# buttons.net
KiCad netlist of a schematic drawn in Altium Designer
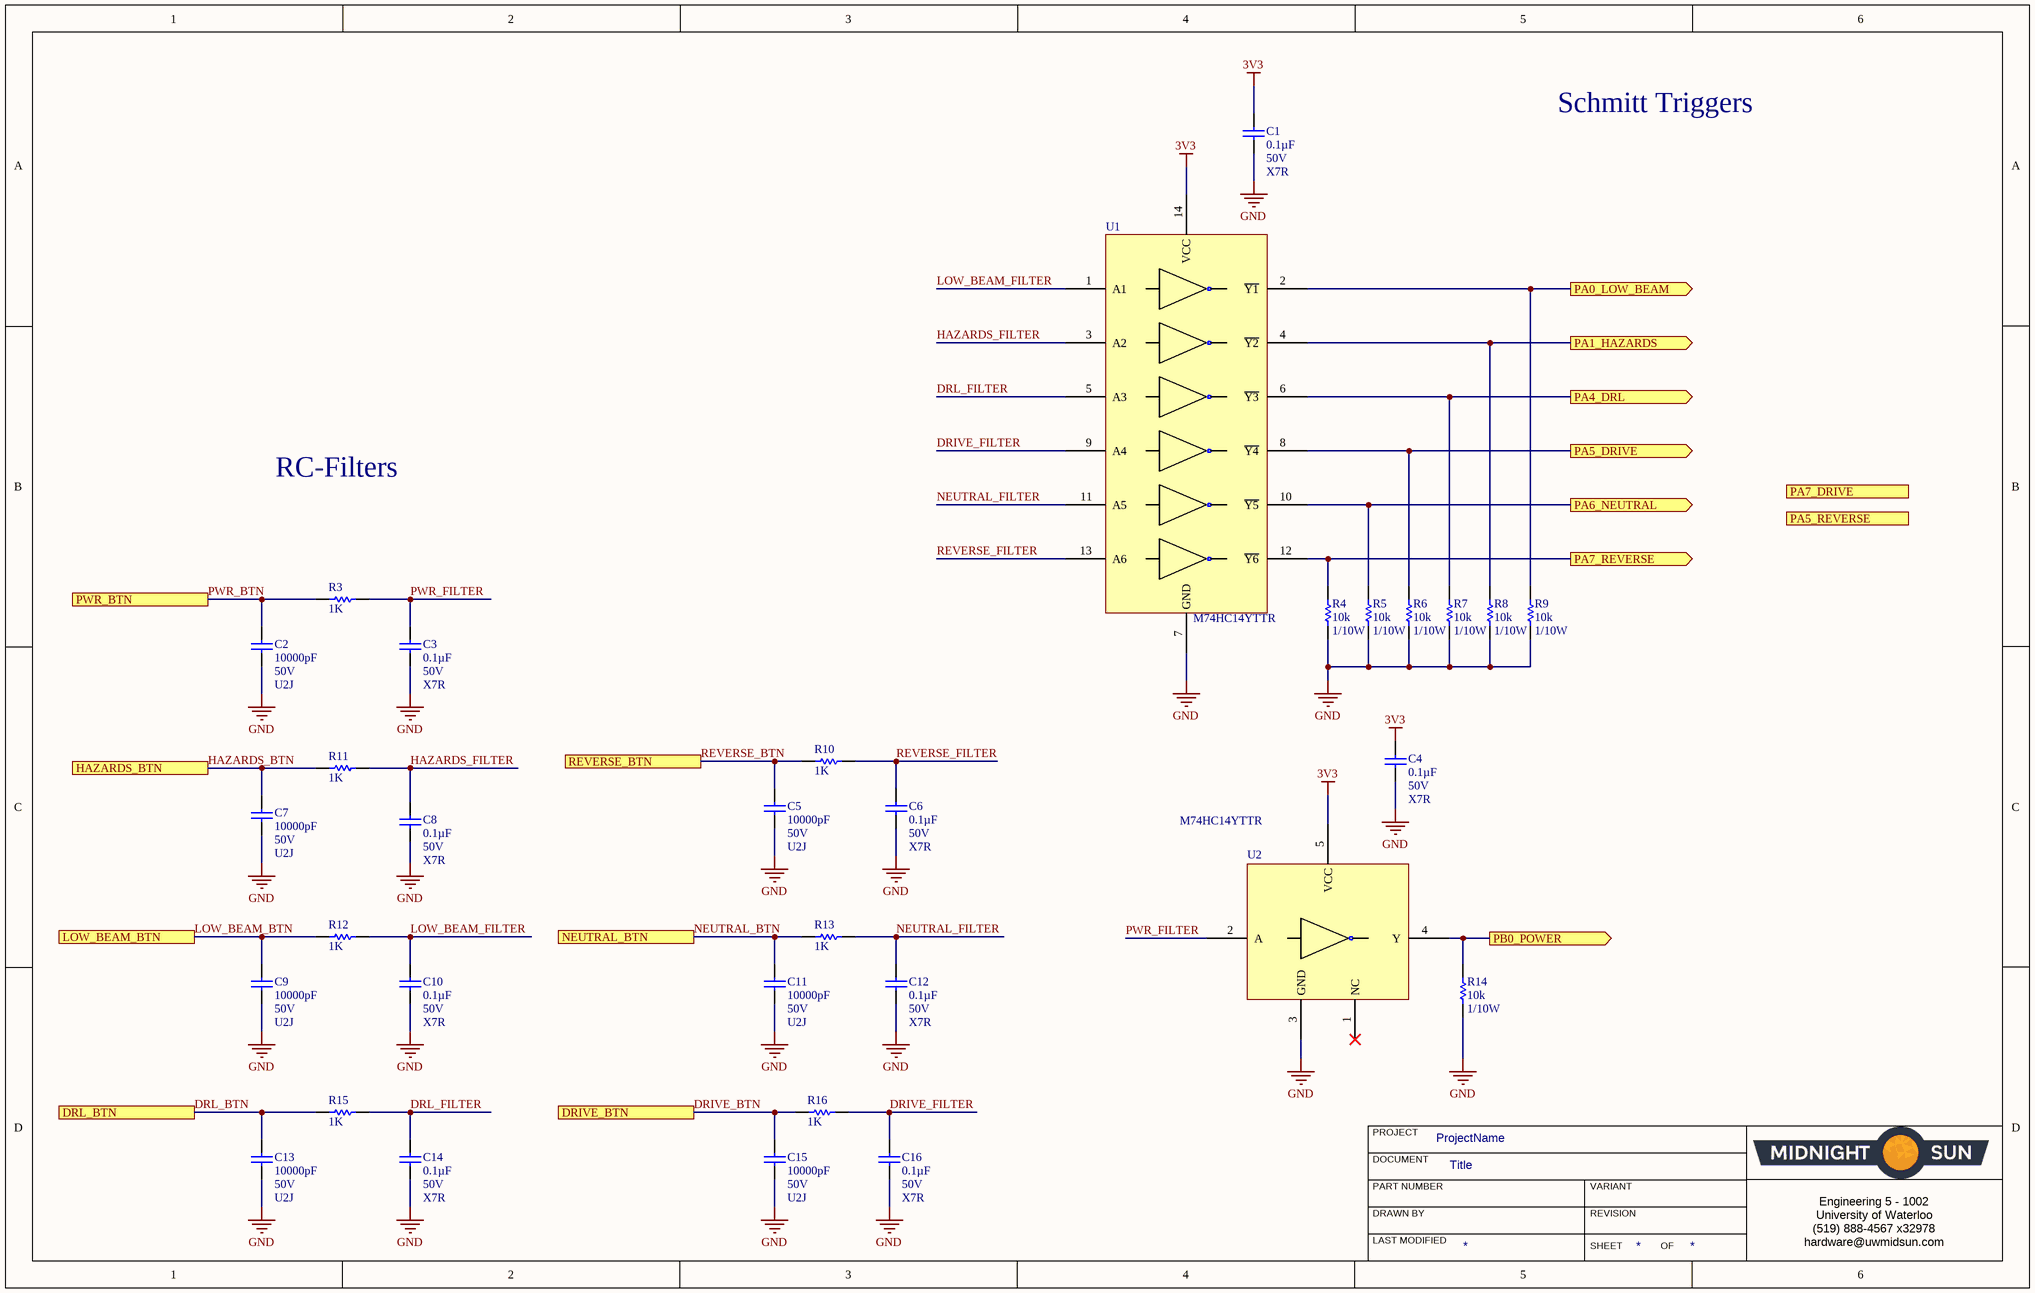
[diagram p0: buttons.SchDoc]

(export (version "E")
  (design (tool "Eeschema 10.0.6"))
  (components
    (comp (ref "C1")
      (value "CAP CER 0.1UF 50V 10% X7R 0603")
      (footprint "CAP, 0603")
      (description "0.10µF ±10% 50V Ceramic Capacitor X7R 0603 (1608 Metric)")
      (fields
        (field (name "TOLERANCE") "±10%")
        (field (name "CAPACITANCE") "0.1µF")
        (field (name "VOLTAGE") "50V")
        (field (name "TEMPERATURE COEFFICIENT") "X7R")
      )
      (libsource (lib "Schematic Diagrams") (part "CAP CER 0.1UF 50V 10% X7R 0603"))
    )
    (comp (ref "C2")
      (value "CAP CER 10nF 50V 5% X7R 0603")
      (footprint "CAP, 0603")
      (description "10000pF ±5% 50V Ceramic Capacitor U2J 0603 (1608 Metric)")
      (fields
        (field (name "TOLERANCE") "±5%")
        (field (name "CAPACITANCE") "10000pF")
        (field (name "VOLTAGE") "50V")
        (field (name "TEMPERATURE COEFFICIENT") "U2J")
      )
      (libsource (lib "altium-import") (part "root_0_CAP CER 10nF 50V 5% X7R 0603_"))
    )
    (comp (ref "C3")
      (value "CAP CER 0.1UF 50V 10% X7R 0603")
      (footprint "CAP, 0603")
      (description "0.10µF ±10% 50V Ceramic Capacitor X7R 0603 (1608 Metric)")
      (fields
        (field (name "TOLERANCE") "±10%")
        (field (name "CAPACITANCE") "0.1µF")
        (field (name "VOLTAGE") "50V")
        (field (name "TEMPERATURE COEFFICIENT") "X7R")
      )
      (libsource (lib "Schematic Diagrams") (part "CAP CER 0.1UF 50V 10% X7R 0603"))
    )
    (comp (ref "C4")
      (value "CAP CER 0.1UF 50V 10% X7R 0603")
      (footprint "CAP, 0603")
      (description "0.10µF ±10% 50V Ceramic Capacitor X7R 0603 (1608 Metric)")
      (fields
        (field (name "TOLERANCE") "±10%")
        (field (name "CAPACITANCE") "0.1µF")
        (field (name "VOLTAGE") "50V")
        (field (name "TEMPERATURE COEFFICIENT") "X7R")
      )
      (libsource (lib "Schematic Diagrams") (part "CAP CER 0.1UF 50V 10% X7R 0603"))
    )
    (comp (ref "C5")
      (value "CAP CER 10nF 50V 5% X7R 0603")
      (footprint "CAP, 0603")
      (description "10000pF ±5% 50V Ceramic Capacitor U2J 0603 (1608 Metric)")
      (fields
        (field (name "TOLERANCE") "±5%")
        (field (name "CAPACITANCE") "10000pF")
        (field (name "VOLTAGE") "50V")
        (field (name "TEMPERATURE COEFFICIENT") "U2J")
      )
      (libsource (lib "altium-import") (part "root_0_CAP CER 10nF 50V 5% X7R 0603_"))
    )
    (comp (ref "C6")
      (value "CAP CER 0.1UF 50V 10% X7R 0603")
      (footprint "CAP, 0603")
      (description "0.10µF ±10% 50V Ceramic Capacitor X7R 0603 (1608 Metric)")
      (fields
        (field (name "TOLERANCE") "±10%")
        (field (name "CAPACITANCE") "0.1µF")
        (field (name "VOLTAGE") "50V")
        (field (name "TEMPERATURE COEFFICIENT") "X7R")
      )
      (libsource (lib "Schematic Diagrams") (part "CAP CER 0.1UF 50V 10% X7R 0603"))
    )
    (comp (ref "C7")
      (value "CAP CER 10nF 50V 5% X7R 0603")
      (footprint "CAP, 0603")
      (description "10000pF ±5% 50V Ceramic Capacitor U2J 0603 (1608 Metric)")
      (fields
        (field (name "TOLERANCE") "±5%")
        (field (name "CAPACITANCE") "10000pF")
        (field (name "VOLTAGE") "50V")
        (field (name "TEMPERATURE COEFFICIENT") "U2J")
      )
      (libsource (lib "altium-import") (part "root_0_CAP CER 10nF 50V 5% X7R 0603_"))
    )
    (comp (ref "C8")
      (value "CAP CER 0.1UF 50V 10% X7R 0603")
      (footprint "CAP, 0603")
      (description "0.10µF ±10% 50V Ceramic Capacitor X7R 0603 (1608 Metric)")
      (fields
        (field (name "TOLERANCE") "±10%")
        (field (name "CAPACITANCE") "0.1µF")
        (field (name "VOLTAGE") "50V")
        (field (name "TEMPERATURE COEFFICIENT") "X7R")
      )
      (libsource (lib "Schematic Diagrams") (part "CAP CER 0.1UF 50V 10% X7R 0603"))
    )
    (comp (ref "C9")
      (value "CAP CER 10nF 50V 5% X7R 0603")
      (footprint "CAP, 0603")
      (description "10000pF ±5% 50V Ceramic Capacitor U2J 0603 (1608 Metric)")
      (fields
        (field (name "TOLERANCE") "±5%")
        (field (name "CAPACITANCE") "10000pF")
        (field (name "VOLTAGE") "50V")
        (field (name "TEMPERATURE COEFFICIENT") "U2J")
      )
      (libsource (lib "altium-import") (part "root_0_CAP CER 10nF 50V 5% X7R 0603_"))
    )
    (comp (ref "C10")
      (value "CAP CER 0.1UF 50V 10% X7R 0603")
      (footprint "CAP, 0603")
      (description "0.10µF ±10% 50V Ceramic Capacitor X7R 0603 (1608 Metric)")
      (fields
        (field (name "TOLERANCE") "±10%")
        (field (name "CAPACITANCE") "0.1µF")
        (field (name "VOLTAGE") "50V")
        (field (name "TEMPERATURE COEFFICIENT") "X7R")
      )
      (libsource (lib "Schematic Diagrams") (part "CAP CER 0.1UF 50V 10% X7R 0603"))
    )
    (comp (ref "C11")
      (value "CAP CER 10nF 50V 5% X7R 0603")
      (footprint "CAP, 0603")
      (description "10000pF ±5% 50V Ceramic Capacitor U2J 0603 (1608 Metric)")
      (fields
        (field (name "TOLERANCE") "±5%")
        (field (name "CAPACITANCE") "10000pF")
        (field (name "VOLTAGE") "50V")
        (field (name "TEMPERATURE COEFFICIENT") "U2J")
      )
      (libsource (lib "altium-import") (part "root_0_CAP CER 10nF 50V 5% X7R 0603_"))
    )
    (comp (ref "C12")
      (value "CAP CER 0.1UF 50V 10% X7R 0603")
      (footprint "CAP, 0603")
      (description "0.10µF ±10% 50V Ceramic Capacitor X7R 0603 (1608 Metric)")
      (fields
        (field (name "TOLERANCE") "±10%")
        (field (name "CAPACITANCE") "0.1µF")
        (field (name "VOLTAGE") "50V")
        (field (name "TEMPERATURE COEFFICIENT") "X7R")
      )
      (libsource (lib "Schematic Diagrams") (part "CAP CER 0.1UF 50V 10% X7R 0603"))
    )
    (comp (ref "C13")
      (value "CAP CER 10nF 50V 5% X7R 0603")
      (footprint "CAP, 0603")
      (description "10000pF ±5% 50V Ceramic Capacitor U2J 0603 (1608 Metric)")
      (fields
        (field (name "TOLERANCE") "±5%")
        (field (name "CAPACITANCE") "10000pF")
        (field (name "VOLTAGE") "50V")
        (field (name "TEMPERATURE COEFFICIENT") "U2J")
      )
      (libsource (lib "altium-import") (part "root_0_CAP CER 10nF 50V 5% X7R 0603_"))
    )
    (comp (ref "C14")
      (value "CAP CER 0.1UF 50V 10% X7R 0603")
      (footprint "CAP, 0603")
      (description "0.10µF ±10% 50V Ceramic Capacitor X7R 0603 (1608 Metric)")
      (fields
        (field (name "TOLERANCE") "±10%")
        (field (name "CAPACITANCE") "0.1µF")
        (field (name "VOLTAGE") "50V")
        (field (name "TEMPERATURE COEFFICIENT") "X7R")
      )
      (libsource (lib "Schematic Diagrams") (part "CAP CER 0.1UF 50V 10% X7R 0603"))
    )
    (comp (ref "C15")
      (value "CAP CER 10nF 50V 5% X7R 0603")
      (footprint "CAP, 0603")
      (description "10000pF ±5% 50V Ceramic Capacitor U2J 0603 (1608 Metric)")
      (fields
        (field (name "TOLERANCE") "±5%")
        (field (name "CAPACITANCE") "10000pF")
        (field (name "VOLTAGE") "50V")
        (field (name "TEMPERATURE COEFFICIENT") "U2J")
      )
      (libsource (lib "altium-import") (part "root_0_CAP CER 10nF 50V 5% X7R 0603_"))
    )
    (comp (ref "C16")
      (value "CAP CER 0.1UF 50V 10% X7R 0603")
      (footprint "CAP, 0603")
      (description "0.10µF ±10% 50V Ceramic Capacitor X7R 0603 (1608 Metric)")
      (fields
        (field (name "TOLERANCE") "±10%")
        (field (name "CAPACITANCE") "0.1µF")
        (field (name "VOLTAGE") "50V")
        (field (name "TEMPERATURE COEFFICIENT") "X7R")
      )
      (libsource (lib "Schematic Diagrams") (part "CAP CER 0.1UF 50V 10% X7R 0603"))
    )
    (comp (ref "R3")
      (value "1K")
      (footprint "RES, 0603")
      (description "1k Ohm ±5% 0.1W, 1/10W Chip Resistor 0603 (1608 Metric)")
      (fields
        (field (name "MANUFACTURER") "Yageo")
        (field (name "MANUFACTURER PART NUMBER") "RC0603JR-071KL")
      )
      (libsource (lib "Schematic Diagrams") (part "RES 1K OHM 5% 1/10W 0603"))
    )
    (comp (ref "R4")
      (value "RES 10K OHM 1% 1/10W 0603")
      (footprint "RES, 0603")
      (description "RES SMD 10K OHM 1% 1/10W 0603")
      (fields
        (field (name "TOLERANCE") "±1%")
        (field (name "RESISTANCE") "10k")
        (field (name "POWER") "1/10W")
      )
      (libsource (lib "altium-import") (part "root_0_RES 10K OHM 1% 1/10W 0603_"))
    )
    (comp (ref "R5")
      (value "RES 10K OHM 1% 1/10W 0603")
      (footprint "RES, 0603")
      (description "RES SMD 10K OHM 1% 1/10W 0603")
      (fields
        (field (name "TOLERANCE") "±1%")
        (field (name "RESISTANCE") "10k")
        (field (name "POWER") "1/10W")
      )
      (libsource (lib "altium-import") (part "root_0_RES 10K OHM 1% 1/10W 0603_"))
    )
    (comp (ref "R6")
      (value "RES 10K OHM 1% 1/10W 0603")
      (footprint "RES, 0603")
      (description "RES SMD 10K OHM 1% 1/10W 0603")
      (fields
        (field (name "TOLERANCE") "±1%")
        (field (name "RESISTANCE") "10k")
        (field (name "POWER") "1/10W")
      )
      (libsource (lib "altium-import") (part "root_0_RES 10K OHM 1% 1/10W 0603_"))
    )
    (comp (ref "R7")
      (value "RES 10K OHM 1% 1/10W 0603")
      (footprint "RES, 0603")
      (description "RES SMD 10K OHM 1% 1/10W 0603")
      (fields
        (field (name "TOLERANCE") "±1%")
        (field (name "RESISTANCE") "10k")
        (field (name "POWER") "1/10W")
      )
      (libsource (lib "altium-import") (part "root_0_RES 10K OHM 1% 1/10W 0603_"))
    )
    (comp (ref "R8")
      (value "RES 10K OHM 1% 1/10W 0603")
      (footprint "RES, 0603")
      (description "RES SMD 10K OHM 1% 1/10W 0603")
      (fields
        (field (name "TOLERANCE") "±1%")
        (field (name "RESISTANCE") "10k")
        (field (name "POWER") "1/10W")
      )
      (libsource (lib "altium-import") (part "root_0_RES 10K OHM 1% 1/10W 0603_"))
    )
    (comp (ref "R9")
      (value "RES 10K OHM 1% 1/10W 0603")
      (footprint "RES, 0603")
      (description "RES SMD 10K OHM 1% 1/10W 0603")
      (fields
        (field (name "TOLERANCE") "±1%")
        (field (name "RESISTANCE") "10k")
        (field (name "POWER") "1/10W")
      )
      (libsource (lib "altium-import") (part "root_0_RES 10K OHM 1% 1/10W 0603_"))
    )
    (comp (ref "R10")
      (value "1K")
      (footprint "RES, 0603")
      (description "1k Ohm ±5% 0.1W, 1/10W Chip Resistor 0603 (1608 Metric)")
      (fields
        (field (name "MANUFACTURER") "Yageo")
        (field (name "MANUFACTURER PART NUMBER") "RC0603JR-071KL")
      )
      (libsource (lib "Schematic Diagrams") (part "RES 1K OHM 5% 1/10W 0603"))
    )
    (comp (ref "R11")
      (value "1K")
      (footprint "RES, 0603")
      (description "1k Ohm ±5% 0.1W, 1/10W Chip Resistor 0603 (1608 Metric)")
      (fields
        (field (name "MANUFACTURER") "Yageo")
        (field (name "MANUFACTURER PART NUMBER") "RC0603JR-071KL")
      )
      (libsource (lib "Schematic Diagrams") (part "RES 1K OHM 5% 1/10W 0603"))
    )
    (comp (ref "R12")
      (value "1K")
      (footprint "RES, 0603")
      (description "1k Ohm ±5% 0.1W, 1/10W Chip Resistor 0603 (1608 Metric)")
      (fields
        (field (name "MANUFACTURER") "Yageo")
        (field (name "MANUFACTURER PART NUMBER") "RC0603JR-071KL")
      )
      (libsource (lib "Schematic Diagrams") (part "RES 1K OHM 5% 1/10W 0603"))
    )
    (comp (ref "R13")
      (value "1K")
      (footprint "RES, 0603")
      (description "1k Ohm ±5% 0.1W, 1/10W Chip Resistor 0603 (1608 Metric)")
      (fields
        (field (name "MANUFACTURER") "Yageo")
        (field (name "MANUFACTURER PART NUMBER") "RC0603JR-071KL")
      )
      (libsource (lib "Schematic Diagrams") (part "RES 1K OHM 5% 1/10W 0603"))
    )
    (comp (ref "R14")
      (value "RES 10K OHM 1% 1/10W 0603")
      (footprint "RES, 0603")
      (description "RES SMD 10K OHM 1% 1/10W 0603")
      (fields
        (field (name "TOLERANCE") "±1%")
        (field (name "RESISTANCE") "10k")
        (field (name "POWER") "1/10W")
      )
      (libsource (lib "altium-import") (part "root_0_RES 10K OHM 1% 1/10W 0603_"))
    )
    (comp (ref "R15")
      (value "1K")
      (footprint "RES, 0603")
      (description "1k Ohm ±5% 0.1W, 1/10W Chip Resistor 0603 (1608 Metric)")
      (fields
        (field (name "MANUFACTURER") "Yageo")
        (field (name "MANUFACTURER PART NUMBER") "RC0603JR-071KL")
      )
      (libsource (lib "Schematic Diagrams") (part "RES 1K OHM 5% 1/10W 0603"))
    )
    (comp (ref "R16")
      (value "1K")
      (footprint "RES, 0603")
      (description "1k Ohm ±5% 0.1W, 1/10W Chip Resistor 0603 (1608 Metric)")
      (fields
        (field (name "MANUFACTURER") "Yageo")
        (field (name "MANUFACTURER PART NUMBER") "RC0603JR-071KL")
      )
      (libsource (lib "Schematic Diagrams") (part "RES 1K OHM 5% 1/10W 0603"))
    )
    (comp (ref "U1")
      (value "IC INVERTER SCHMITT 6CH 14TSSOP")
      (footprint "IC INVERTER SCHMITT 6CH 14TSSOP")
      (description "Inverter IC 6 Channel Schmitt Trigger 14-TSSOP")
      (fields
        (field (name "MANUFACTURER") "STMicroelectronics")
        (field (name "MANUFACTURER PART NUMBER") "M74HC14YTTR")
      )
      (libsource (lib "Schematic Diagrams") (part "IC INVERTER SCHMITT 6CH 14TSSOP"))
    )
    (comp (ref "U2")
      (value "IC INVERTER SCHMITT 1CH SC70-5")
      (footprint "IC INVERTER SCHMITT 1CH SC70-5")
      (description "Inverter IC 1 Channel Schmitt Trigger SC-70-5")
      (fields
        (field (name "MANUFACTURER") "STMicroelectronics")
        (field (name "MANUFACTURER PART NUMBER") "M74HC14YTTR")
      )
      (libsource (lib "Schematic Diagrams") (part "IC INVERTER SCHMITT 1CH SC70-5"))
    )
  )
  (nets
    (net (code "1") (name "/DRIVE_BTN") (class "Default")
      (node (ref "C15") (pin "1") (pinfunction "1_1") (pintype "passive"))
      (node (ref "R16") (pin "1") (pinfunction "1_1") (pintype "passive"))
    )
    (net (code "2") (name "/DRIVE_FILTER") (class "Default")
      (node (ref "C16") (pin "1") (pinfunction "1_1") (pintype "passive"))
      (node (ref "R16") (pin "2") (pinfunction "2_2") (pintype "passive"))
      (node (ref "U1") (pin "9") (pinfunction "A4_9") (pintype "passive"))
    )
    (net (code "3") (name "/DRL_BTN") (class "Default")
      (node (ref "C13") (pin "1") (pinfunction "1_1") (pintype "passive"))
      (node (ref "R15") (pin "1") (pinfunction "1_1") (pintype "passive"))
    )
    (net (code "4") (name "/DRL_FILTER") (class "Default")
      (node (ref "C14") (pin "1") (pinfunction "1_1") (pintype "passive"))
      (node (ref "R15") (pin "2") (pinfunction "2_2") (pintype "passive"))
      (node (ref "U1") (pin "5") (pinfunction "A3_5") (pintype "passive"))
    )
    (net (code "5") (name "/HAZARDS_BTN") (class "Default")
      (node (ref "C7") (pin "1") (pinfunction "1_1") (pintype "passive"))
      (node (ref "R11") (pin "1") (pinfunction "1_1") (pintype "passive"))
    )
    (net (code "6") (name "/HAZARDS_FILTER") (class "Default")
      (node (ref "C8") (pin "1") (pinfunction "1_1") (pintype "passive"))
      (node (ref "R11") (pin "2") (pinfunction "2_2") (pintype "passive"))
      (node (ref "U1") (pin "3") (pinfunction "A2_3") (pintype "passive"))
    )
    (net (code "7") (name "/LOW_BEAM_BTN") (class "Default")
      (node (ref "C9") (pin "1") (pinfunction "1_1") (pintype "passive"))
      (node (ref "R12") (pin "1") (pinfunction "1_1") (pintype "passive"))
    )
    (net (code "8") (name "/LOW_BEAM_FILTER") (class "Default")
      (node (ref "C10") (pin "1") (pinfunction "1_1") (pintype "passive"))
      (node (ref "R12") (pin "2") (pinfunction "2_2") (pintype "passive"))
      (node (ref "U1") (pin "1") (pinfunction "A1_1") (pintype "passive"))
    )
    (net (code "9") (name "/NEUTRAL_BTN") (class "Default")
      (node (ref "C11") (pin "1") (pinfunction "1_1") (pintype "passive"))
      (node (ref "R13") (pin "1") (pinfunction "1_1") (pintype "passive"))
    )
    (net (code "10") (name "/NEUTRAL_FILTER") (class "Default")
      (node (ref "C12") (pin "1") (pinfunction "1_1") (pintype "passive"))
      (node (ref "R13") (pin "2") (pinfunction "2_2") (pintype "passive"))
      (node (ref "U1") (pin "11") (pinfunction "A5_11") (pintype "passive"))
    )
    (net (code "11") (name "/PA0_LOW_BEAM") (class "Default")
      (node (ref "R9") (pin "1") (pinfunction "1_1") (pintype "passive"))
      (node (ref "U1") (pin "2") (pinfunction "~{Y1}_2") (pintype "passive"))
    )
    (net (code "12") (name "/PA1_HAZARDS") (class "Default")
      (node (ref "R8") (pin "1") (pinfunction "1_1") (pintype "passive"))
      (node (ref "U1") (pin "4") (pinfunction "~{Y2}_4") (pintype "passive"))
    )
    (net (code "13") (name "/PA4_DRL") (class "Default")
      (node (ref "R7") (pin "1") (pinfunction "1_1") (pintype "passive"))
      (node (ref "U1") (pin "6") (pinfunction "~{Y3}_6") (pintype "passive"))
    )
    (net (code "14") (name "/PA5_DRIVE") (class "Default")
      (node (ref "R6") (pin "1") (pinfunction "1_1") (pintype "passive"))
      (node (ref "U1") (pin "8") (pinfunction "~{Y4}_8") (pintype "passive"))
    )
    (net (code "16") (name "/PA6_NEUTRAL") (class "Default")
      (node (ref "R5") (pin "1") (pinfunction "1_1") (pintype "passive"))
      (node (ref "U1") (pin "10") (pinfunction "~{Y5}_10") (pintype "passive"))
    )
    (net (code "18") (name "/PA7_REVERSE") (class "Default")
      (node (ref "R4") (pin "1") (pinfunction "1_1") (pintype "passive"))
      (node (ref "U1") (pin "12") (pinfunction "~{Y6}_12") (pintype "passive"))
    )
    (net (code "19") (name "/PB0_POWER") (class "Default")
      (node (ref "R14") (pin "1") (pinfunction "1_1") (pintype "passive"))
      (node (ref "U2") (pin "4") (pinfunction "Y_4") (pintype "passive"))
    )
    (net (code "20") (name "/PWR_BTN") (class "Default")
      (node (ref "C2") (pin "1") (pinfunction "1_1") (pintype "passive"))
      (node (ref "R3") (pin "1") (pinfunction "1_1") (pintype "passive"))
    )
    (net (code "21") (name "/PWR_FILTER") (class "Default")
      (node (ref "C3") (pin "1") (pinfunction "1_1") (pintype "passive"))
      (node (ref "R3") (pin "2") (pinfunction "2_2") (pintype "passive"))
      (node (ref "U2") (pin "2") (pinfunction "A_2") (pintype "passive"))
    )
    (net (code "22") (name "/REVERSE_BTN") (class "Default")
      (node (ref "C5") (pin "1") (pinfunction "1_1") (pintype "passive"))
      (node (ref "R10") (pin "1") (pinfunction "1_1") (pintype "passive"))
    )
    (net (code "23") (name "/REVERSE_FILTER") (class "Default")
      (node (ref "C6") (pin "1") (pinfunction "1_1") (pintype "passive"))
      (node (ref "R10") (pin "2") (pinfunction "2_2") (pintype "passive"))
      (node (ref "U1") (pin "13") (pinfunction "A6_13") (pintype "passive"))
    )
    (net (code "24") (name "3V3") (class "Default")
      (node (ref "C1") (pin "1") (pinfunction "1_1") (pintype "passive"))
      (node (ref "C4") (pin "1") (pinfunction "1_1") (pintype "passive"))
      (node (ref "U1") (pin "14") (pinfunction "VCC_14") (pintype "passive"))
      (node (ref "U2") (pin "5") (pinfunction "VCC_5") (pintype "passive"))
    )
    (net (code "25") (name "GND") (class "Default")
      (node (ref "C1") (pin "2") (pinfunction "2_2") (pintype "passive"))
      (node (ref "C10") (pin "2") (pinfunction "2_2") (pintype "passive"))
      (node (ref "C11") (pin "2") (pinfunction "2_2") (pintype "passive"))
      (node (ref "C12") (pin "2") (pinfunction "2_2") (pintype "passive"))
      (node (ref "C13") (pin "2") (pinfunction "2_2") (pintype "passive"))
      (node (ref "C14") (pin "2") (pinfunction "2_2") (pintype "passive"))
      (node (ref "C15") (pin "2") (pinfunction "2_2") (pintype "passive"))
      (node (ref "C16") (pin "2") (pinfunction "2_2") (pintype "passive"))
      (node (ref "C2") (pin "2") (pinfunction "2_2") (pintype "passive"))
      (node (ref "C3") (pin "2") (pinfunction "2_2") (pintype "passive"))
      (node (ref "C4") (pin "2") (pinfunction "2_2") (pintype "passive"))
      (node (ref "C5") (pin "2") (pinfunction "2_2") (pintype "passive"))
      (node (ref "C6") (pin "2") (pinfunction "2_2") (pintype "passive"))
      (node (ref "C7") (pin "2") (pinfunction "2_2") (pintype "passive"))
      (node (ref "C8") (pin "2") (pinfunction "2_2") (pintype "passive"))
      (node (ref "C9") (pin "2") (pinfunction "2_2") (pintype "passive"))
      (node (ref "R14") (pin "2") (pinfunction "2_2") (pintype "passive"))
      (node (ref "R4") (pin "2") (pinfunction "2_2") (pintype "passive"))
      (node (ref "R5") (pin "2") (pinfunction "2_2") (pintype "passive"))
      (node (ref "R6") (pin "2") (pinfunction "2_2") (pintype "passive"))
      (node (ref "R7") (pin "2") (pinfunction "2_2") (pintype "passive"))
      (node (ref "R8") (pin "2") (pinfunction "2_2") (pintype "passive"))
      (node (ref "R9") (pin "2") (pinfunction "2_2") (pintype "passive"))
      (node (ref "U1") (pin "7") (pinfunction "GND_7") (pintype "passive"))
      (node (ref "U2") (pin "3") (pinfunction "GND_3") (pintype "passive"))
    )
    (net (code "26") (name "unconnected-(U2-NC-Pad1)") (class "Default")
      (node (ref "U2") (pin "1") (pinfunction "NC_1") (pintype "passive+no_connect"))
    )
  )
)
